# Sequantial_Cell_Switching.net
KiCad netlist of a schematic drawn in Altium Designer
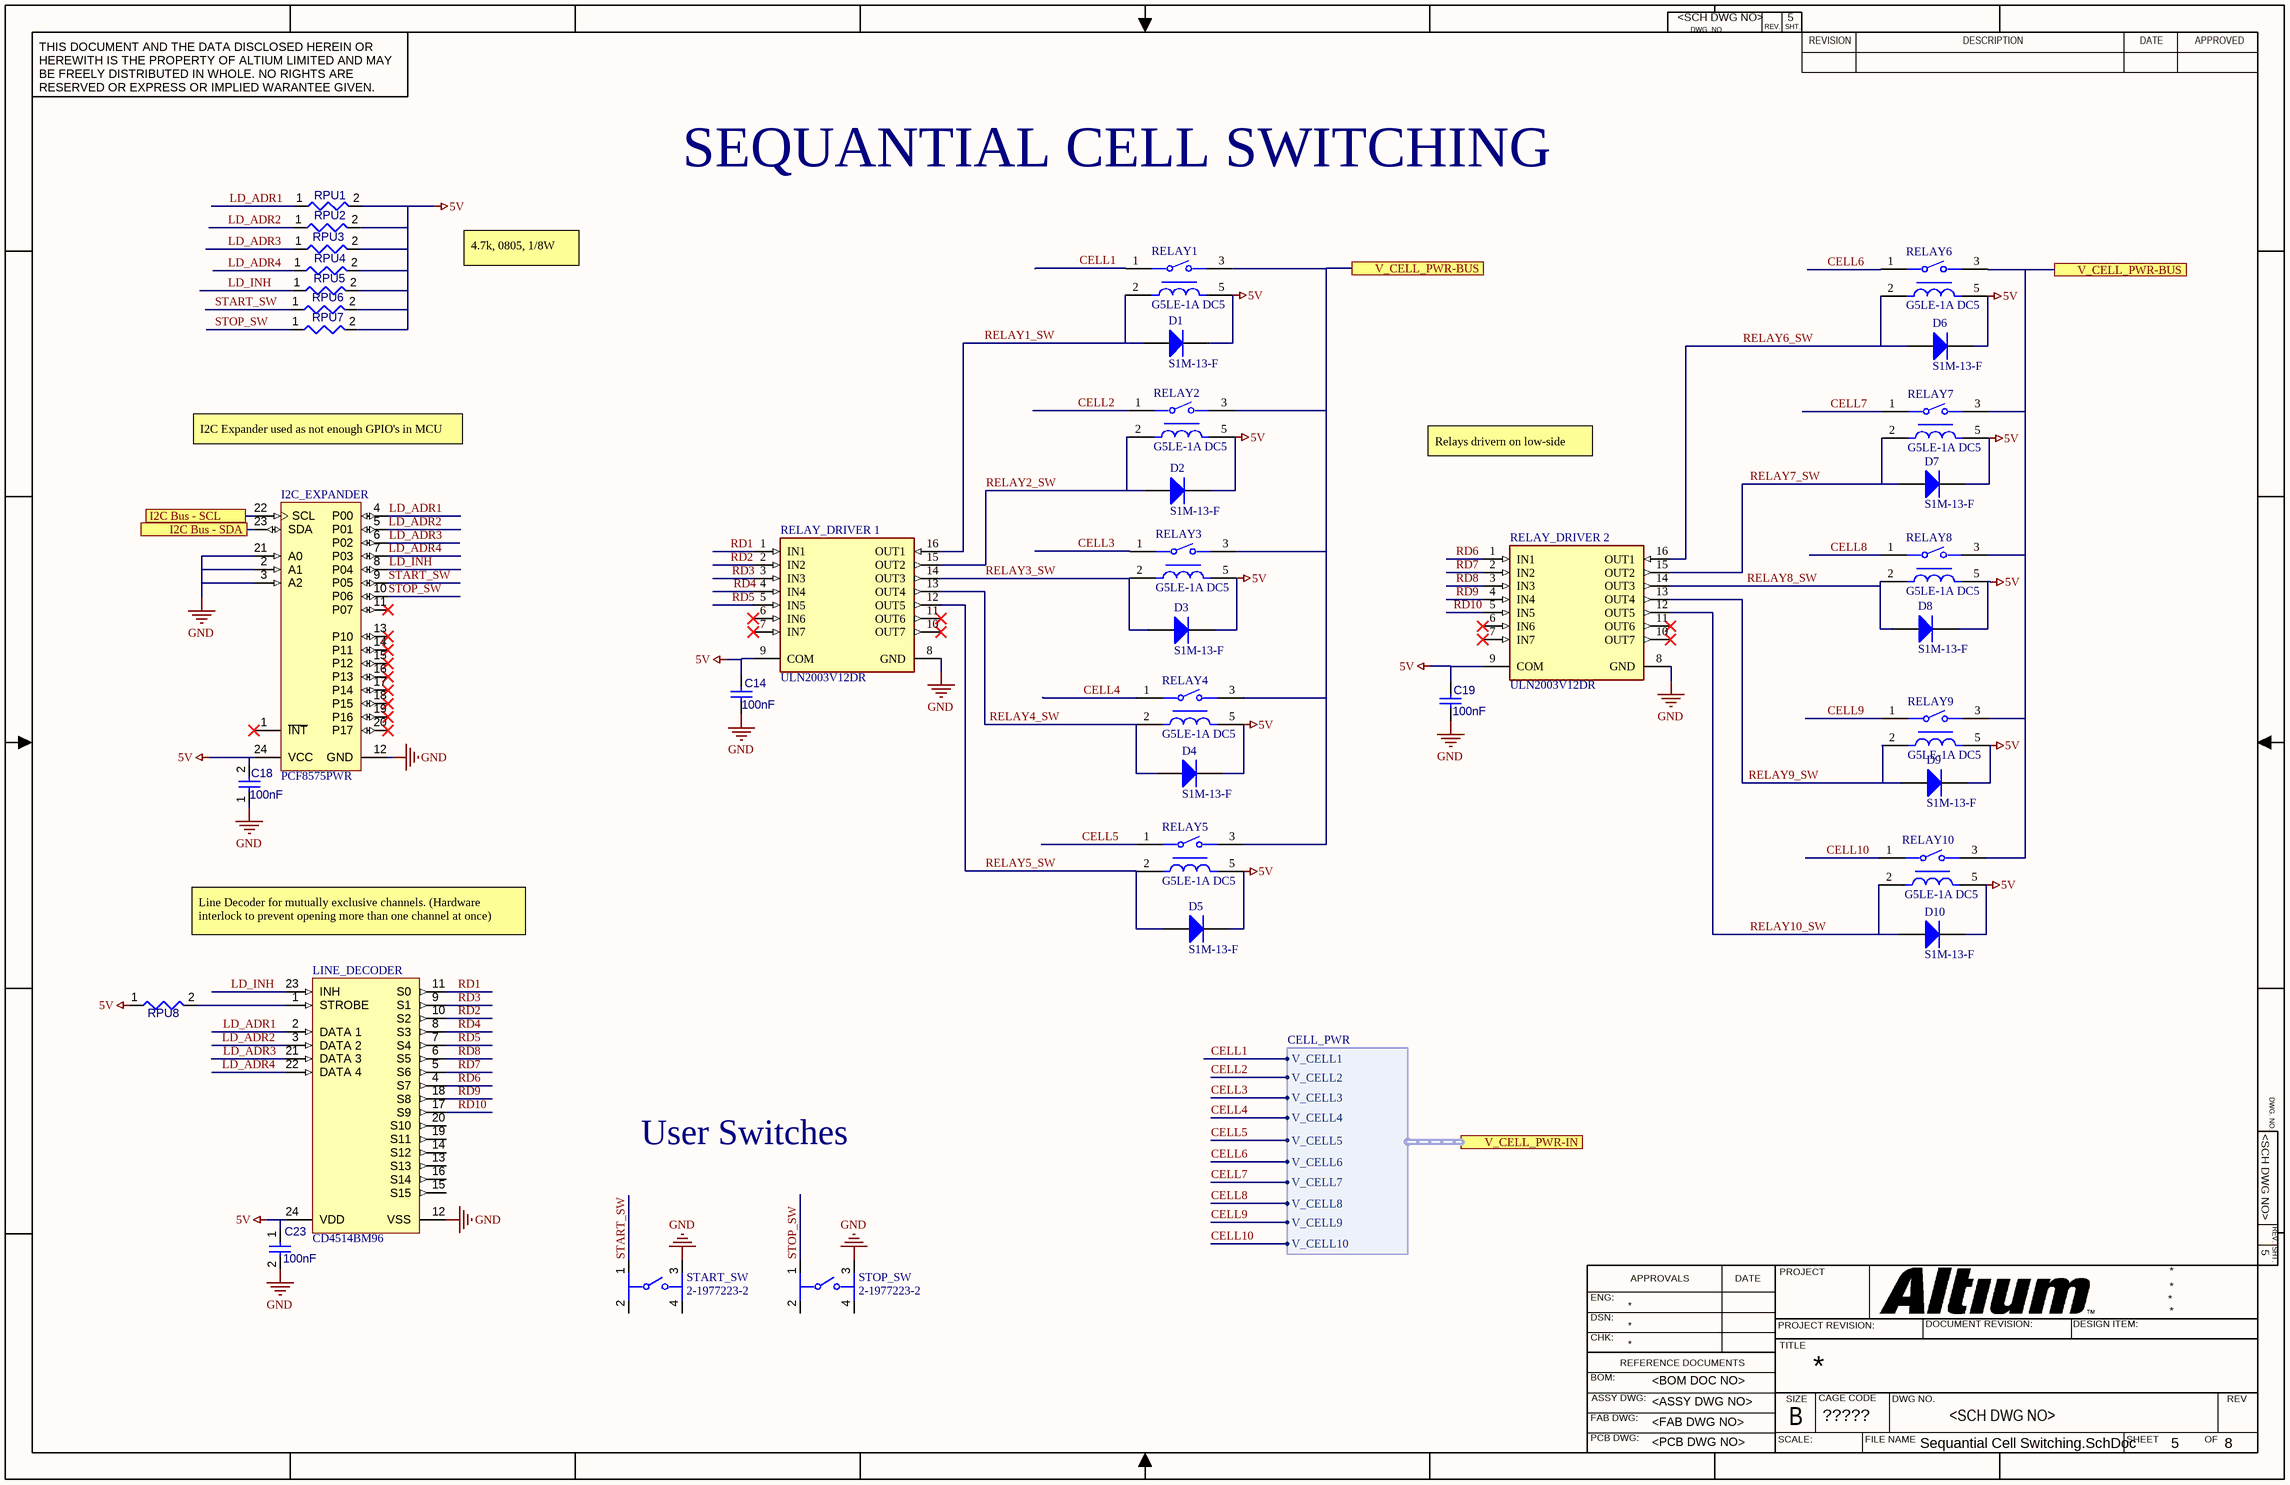
[diagram p0: Sequantial Cell Switching.SchDoc]

(export (version "E")
  (design (tool "Eeschema 10.0.6"))
  (components
    (comp (ref "C14")
      (value "100nF")
      (footprint "CAPC2013X95X50LL10T25")
      (description "Capacitor 100 nF +/-10% 50 V 0805")
      (fields (field (name "TOLERANCE") "10%"))
      (libsource (lib "gugan Sivakumar") (part "CAP-NP-2"))
    )
    (comp (ref "C18")
      (value "100nF")
      (footprint "CAPC2013X95X50LL10T25")
      (description "Capacitor 100 nF +/-10% 50 V 0805")
      (fields (field (name "TOLERANCE") "10%"))
      (libsource (lib "") (part "CAP-NP-2_1"))
    )
    (comp (ref "C19")
      (value "100nF")
      (footprint "CAPC2013X95X50LL10T25")
      (description "Capacitor 100 nF +/-10% 50 V 0805")
      (fields (field (name "TOLERANCE") "10%"))
      (libsource (lib "gugan Sivakumar") (part "CAP-NP-2"))
    )
    (comp (ref "C23")
      (value "100nF")
      (footprint "CAPC2013X95X50LL10T25")
      (description "Capacitor 100 nF +/-10% 50 V 0805")
      (fields (field (name "TOLERANCE") "10%"))
      (libsource (lib "") (part "CAP-NP-2_1"))
    )
    (comp (ref "D1")
      (value "S1M-13-F")
      (footprint "DIOD-S1M-13-F-SMA-2_V")
      (fields (field (name "MANUFACTURER") "Diodes Inc"))
      (libsource (lib "Altium Content Vault") (part "DIOD-D-A1K2-2"))
    )
    (comp (ref "D2")
      (value "S1M-13-F")
      (footprint "DIOD-S1M-13-F-SMA-2_V")
      (fields (field (name "MANUFACTURER") "Diodes Inc"))
      (libsource (lib "Altium Content Vault") (part "DIOD-D-A1K2-2"))
    )
    (comp (ref "D3")
      (value "S1M-13-F")
      (footprint "DIOD-S1M-13-F-SMA-2_V")
      (fields (field (name "MANUFACTURER") "Diodes Inc"))
      (libsource (lib "Altium Content Vault") (part "DIOD-D-A1K2-2"))
    )
    (comp (ref "D4")
      (value "S1M-13-F")
      (footprint "DIOD-S1M-13-F-SMA-2_V")
      (fields (field (name "MANUFACTURER") "Diodes Inc"))
      (libsource (lib "Altium Content Vault") (part "DIOD-D-A1K2-2"))
    )
    (comp (ref "D5")
      (value "S1M-13-F")
      (footprint "DIOD-S1M-13-F-SMA-2_V")
      (fields (field (name "MANUFACTURER") "Diodes Inc"))
      (libsource (lib "Altium Content Vault") (part "DIOD-D-A1K2-2"))
    )
    (comp (ref "D6")
      (value "S1M-13-F")
      (footprint "DIOD-S1M-13-F-SMA-2_V")
      (fields (field (name "MANUFACTURER") "Diodes Inc"))
      (libsource (lib "Altium Content Vault") (part "DIOD-D-A1K2-2"))
    )
    (comp (ref "D7")
      (value "S1M-13-F")
      (footprint "DIOD-S1M-13-F-SMA-2_V")
      (fields (field (name "MANUFACTURER") "Diodes Inc"))
      (libsource (lib "Altium Content Vault") (part "DIOD-D-A1K2-2"))
    )
    (comp (ref "D8")
      (value "S1M-13-F")
      (footprint "DIOD-S1M-13-F-SMA-2_V")
      (fields (field (name "MANUFACTURER") "Diodes Inc"))
      (libsource (lib "Altium Content Vault") (part "DIOD-D-A1K2-2"))
    )
    (comp (ref "D9")
      (value "S1M-13-F")
      (footprint "DIOD-S1M-13-F-SMA-2_V")
      (fields (field (name "MANUFACTURER") "Diodes Inc"))
      (libsource (lib "Altium Content Vault") (part "DIOD-D-A1K2-2"))
    )
    (comp (ref "D10")
      (value "S1M-13-F")
      (footprint "DIOD-S1M-13-F-SMA-2_V")
      (fields (field (name "MANUFACTURER") "Diodes Inc"))
      (libsource (lib "Altium Content Vault") (part "DIOD-D-A1K2-2"))
    )
    (comp (ref "I2C_EXPANDER")
      (value "PCF8575PWR")
      (footprint "PW0024A_L")
      (fields (field (name "MANUFACTURER") "Texas Instruments"))
      (libsource (lib "Altium Content Vault") (part "TI-PCF8575-TSSOP_PW-24"))
    )
    (comp (ref "LINE_DECODER")
      (value "CD4514BM96")
      (footprint "DW0024A_N")
      (description "CMOS 4-Bit Latch/4-to-16 Line Decoder with Output 'High' on Select, DW0024A, LARGE T&R")
      (fields
        (field (name "GENERIC PART NUMBER") "CD4514B")
        (field (name "MANUFACTURER") "Texas Instruments")
      )
      (libsource (lib "Altium Content Vault") (part "TI-CD451XB-24"))
    )
    (comp (ref "RELAY1")
      (value "G5LE-1A DC5")
      (footprint "FP-G5LE-1A_DC5-MFG")
      (description "RELAY GEN PURPOSE SPST 10A 5V")
      (libsource (lib "Altium Content Vault") (part "6e495d724dc645a58f977e2129b87ff"))
    )
    (comp (ref "RELAY2")
      (value "G5LE-1A DC5")
      (footprint "FP-G5LE-1A_DC5-MFG")
      (description "RELAY GEN PURPOSE SPST 10A 5V")
      (libsource (lib "Altium Content Vault") (part "6e495d724dc645a58f977e2129b87ff"))
    )
    (comp (ref "RELAY3")
      (value "G5LE-1A DC5")
      (footprint "FP-G5LE-1A_DC5-MFG")
      (description "RELAY GEN PURPOSE SPST 10A 5V")
      (libsource (lib "Altium Content Vault") (part "6e495d724dc645a58f977e2129b87ff"))
    )
    (comp (ref "RELAY4")
      (value "G5LE-1A DC5")
      (footprint "FP-G5LE-1A_DC5-MFG")
      (description "RELAY GEN PURPOSE SPST 10A 5V")
      (libsource (lib "Altium Content Vault") (part "6e495d724dc645a58f977e2129b87ff"))
    )
    (comp (ref "RELAY5")
      (value "G5LE-1A DC5")
      (footprint "FP-G5LE-1A_DC5-MFG")
      (description "RELAY GEN PURPOSE SPST 10A 5V")
      (libsource (lib "Altium Content Vault") (part "6e495d724dc645a58f977e2129b87ff"))
    )
    (comp (ref "RELAY6")
      (value "G5LE-1A DC5")
      (footprint "FP-G5LE-1A_DC5-MFG")
      (description "RELAY GEN PURPOSE SPST 10A 5V")
      (libsource (lib "Altium Content Vault") (part "6e495d724dc645a58f977e2129b87ff"))
    )
    (comp (ref "RELAY7")
      (value "G5LE-1A DC5")
      (footprint "FP-G5LE-1A_DC5-MFG")
      (description "RELAY GEN PURPOSE SPST 10A 5V")
      (libsource (lib "Altium Content Vault") (part "6e495d724dc645a58f977e2129b87ff"))
    )
    (comp (ref "RELAY8")
      (value "G5LE-1A DC5")
      (footprint "FP-G5LE-1A_DC5-MFG")
      (description "RELAY GEN PURPOSE SPST 10A 5V")
      (libsource (lib "Altium Content Vault") (part "6e495d724dc645a58f977e2129b87ff"))
    )
    (comp (ref "RELAY9")
      (value "G5LE-1A DC5")
      (footprint "FP-G5LE-1A_DC5-MFG")
      (description "RELAY GEN PURPOSE SPST 10A 5V")
      (libsource (lib "Altium Content Vault") (part "6e495d724dc645a58f977e2129b87ff"))
    )
    (comp (ref "RELAY10")
      (value "G5LE-1A DC5")
      (footprint "FP-G5LE-1A_DC5-MFG")
      (description "RELAY GEN PURPOSE SPST 10A 5V")
      (libsource (lib "Altium Content Vault") (part "6e495d724dc645a58f977e2129b87ff"))
    )
    (comp (ref "RELAY_DRIVER 1")
      (value "ULN2003V12DR")
      (footprint "FP-D0016A-MFG")
      (description "MOSFET 7CH 16SOIC")
      (libsource (lib "Altium Content Vault") (part "1bf5c18f3aeaca83cb90dec63c1b343"))
    )
    (comp (ref "RELAY_DRIVER 2")
      (value "ULN2003V12DR")
      (footprint "FP-D0016A-MFG")
      (description "MOSFET 7CH 16SOIC")
      (libsource (lib "Altium Content Vault") (part "1bf5c18f3aeaca83cb90dec63c1b343"))
    )
    (comp (ref "RPU1")
      (value "Resistor 4k7 +/-1% 0805 125 mW")
      (footprint "RESC2013X70X40ML20T20")
      (description "Chip Resistor, 4.7 KOhm, +/- 1%, 0.125 W, -55 to 155 degC, 0805 (2012 Metric)")
      (fields (field (name "TOLERANCE") "1%") (field (name "POWER") "125mW"))
      (libsource (lib "gugan Sivakumar") (part "RES-2"))
    )
    (comp (ref "RPU2")
      (value "Resistor 4k7 +/-1% 0805 125 mW")
      (footprint "RESC2013X70X40ML20T20")
      (description "Chip Resistor, 4.7 KOhm, +/- 1%, 0.125 W, -55 to 155 degC, 0805 (2012 Metric)")
      (fields (field (name "TOLERANCE") "1%") (field (name "POWER") "125mW"))
      (libsource (lib "gugan Sivakumar") (part "RES-2"))
    )
    (comp (ref "RPU3")
      (value "Resistor 4k7 +/-1% 0805 125 mW")
      (footprint "RESC2013X70X40ML20T20")
      (description "Chip Resistor, 4.7 KOhm, +/- 1%, 0.125 W, -55 to 155 degC, 0805 (2012 Metric)")
      (fields (field (name "TOLERANCE") "1%") (field (name "POWER") "125mW"))
      (libsource (lib "gugan Sivakumar") (part "RES-2"))
    )
    (comp (ref "RPU4")
      (value "Resistor 4k7 +/-1% 0805 125 mW")
      (footprint "RESC2013X70X40ML20T20")
      (description "Chip Resistor, 4.7 KOhm, +/- 1%, 0.125 W, -55 to 155 degC, 0805 (2012 Metric)")
      (fields (field (name "TOLERANCE") "1%") (field (name "POWER") "125mW"))
      (libsource (lib "gugan Sivakumar") (part "RES-2"))
    )
    (comp (ref "RPU5")
      (value "Resistor 4k7 +/-1% 0805 125 mW")
      (footprint "RESC2013X70X40ML20T20")
      (description "Chip Resistor, 4.7 KOhm, +/- 1%, 0.125 W, -55 to 155 degC, 0805 (2012 Metric)")
      (fields (field (name "TOLERANCE") "1%") (field (name "POWER") "125mW"))
      (libsource (lib "gugan Sivakumar") (part "RES-2"))
    )
    (comp (ref "RPU6")
      (value "Resistor 4k7 +/-1% 0805 125 mW")
      (footprint "RESC2013X70X40ML20T20")
      (description "Chip Resistor, 4.7 KOhm, +/- 1%, 0.125 W, -55 to 155 degC, 0805 (2012 Metric)")
      (fields (field (name "TOLERANCE") "1%") (field (name "POWER") "125mW"))
      (libsource (lib "gugan Sivakumar") (part "RES-2"))
    )
    (comp (ref "RPU7")
      (value "Resistor 4k7 +/-1% 0805 125 mW")
      (footprint "RESC2013X70X40ML20T20")
      (description "Chip Resistor, 4.7 KOhm, +/- 1%, 0.125 W, -55 to 155 degC, 0805 (2012 Metric)")
      (fields (field (name "TOLERANCE") "1%") (field (name "POWER") "125mW"))
      (libsource (lib "gugan Sivakumar") (part "RES-2"))
    )
    (comp (ref "RPU8")
      (value "Resistor 4k7 +/-1% 0805 125 mW")
      (footprint "RESC2013X70X40ML20T20")
      (description "Chip Resistor, 4.7 KOhm, +/- 1%, 0.125 W, -55 to 155 degC, 0805 (2012 Metric)")
      (fields (field (name "TOLERANCE") "1%") (field (name "POWER") "125mW"))
      (libsource (lib "gugan Sivakumar") (part "RES-2"))
    )
    (comp (ref "START_SW")
      (value "2-1977223-2")
      (footprint "FP-2-1977223-2-MFG")
      (description "SWITCH TACTILE SPST-NO 0.05A 24V")
      (libsource (lib "Altium Content Vault") (part "b8895f3f4cefb76e1819d2863dba89b"))
    )
    (comp (ref "STOP_SW")
      (value "2-1977223-2")
      (footprint "FP-2-1977223-2-MFG")
      (description "SWITCH TACTILE SPST-NO 0.05A 24V")
      (libsource (lib "Altium Content Vault") (part "b8895f3f4cefb76e1819d2863dba89b"))
    )
  )
  (nets
    (net (code "2") (name "/CELL1") (class "Default")
      (node (ref "RELAY1") (pin "1") (pinfunction "1_1") (pintype "passive"))
    )
    (net (code "3") (name "/CELL2") (class "Default")
      (node (ref "RELAY2") (pin "1") (pinfunction "1_1") (pintype "passive"))
    )
    (net (code "4") (name "/CELL3") (class "Default")
      (node (ref "RELAY3") (pin "1") (pinfunction "1_1") (pintype "passive"))
    )
    (net (code "5") (name "/CELL4") (class "Default")
      (node (ref "RELAY4") (pin "1") (pinfunction "1_1") (pintype "passive"))
    )
    (net (code "6") (name "/CELL5") (class "Default")
      (node (ref "RELAY5") (pin "1") (pinfunction "1_1") (pintype "passive"))
    )
    (net (code "7") (name "/CELL6") (class "Default")
      (node (ref "RELAY6") (pin "1") (pinfunction "1_1") (pintype "passive"))
    )
    (net (code "8") (name "/CELL7") (class "Default")
      (node (ref "RELAY7") (pin "1") (pinfunction "1_1") (pintype "passive"))
    )
    (net (code "9") (name "/CELL8") (class "Default")
      (node (ref "RELAY8") (pin "1") (pinfunction "1_1") (pintype "passive"))
    )
    (net (code "10") (name "/CELL9") (class "Default")
      (node (ref "RELAY9") (pin "1") (pinfunction "1_1") (pintype "passive"))
    )
    (net (code "11") (name "/CELL10") (class "Default")
      (node (ref "RELAY10") (pin "1") (pinfunction "1_1") (pintype "passive"))
    )
    (net (code "12") (name "/I2C Bus - SCL") (class "Default")
      (node (ref "I2C_EXPANDER") (pin "22") (pinfunction "SCL_22") (pintype "input"))
    )
    (net (code "13") (name "/I2C Bus - SDA") (class "Default")
      (node (ref "I2C_EXPANDER") (pin "23") (pinfunction "SDA_23") (pintype "bidirectional"))
    )
    (net (code "14") (name "/LD_ADR1") (class "Default")
      (node (ref "I2C_EXPANDER") (pin "4") (pinfunction "P00_4") (pintype "bidirectional"))
      (node (ref "LINE_DECODER") (pin "2") (pinfunction "DATA_1_2") (pintype "input"))
      (node (ref "RPU1") (pin "1") (pinfunction "1_1") (pintype "passive"))
    )
    (net (code "15") (name "/LD_ADR2") (class "Default")
      (node (ref "I2C_EXPANDER") (pin "5") (pinfunction "P01_5") (pintype "bidirectional"))
      (node (ref "LINE_DECODER") (pin "3") (pinfunction "DATA_2_3") (pintype "input"))
      (node (ref "RPU2") (pin "1") (pinfunction "1_1") (pintype "passive"))
    )
    (net (code "16") (name "/LD_ADR3") (class "Default")
      (node (ref "I2C_EXPANDER") (pin "6") (pinfunction "P02_6") (pintype "bidirectional"))
      (node (ref "LINE_DECODER") (pin "21") (pinfunction "DATA_3_21") (pintype "input"))
      (node (ref "RPU3") (pin "1") (pinfunction "1_1") (pintype "passive"))
    )
    (net (code "17") (name "/LD_ADR4") (class "Default")
      (node (ref "I2C_EXPANDER") (pin "7") (pinfunction "P03_7") (pintype "bidirectional"))
      (node (ref "LINE_DECODER") (pin "22") (pinfunction "DATA_4_22") (pintype "input"))
      (node (ref "RPU4") (pin "1") (pinfunction "1_1") (pintype "passive"))
    )
    (net (code "18") (name "/LD_INH") (class "Default")
      (node (ref "I2C_EXPANDER") (pin "8") (pinfunction "P04_8") (pintype "bidirectional"))
      (node (ref "LINE_DECODER") (pin "23") (pinfunction "INH_23") (pintype "input"))
      (node (ref "RPU5") (pin "1") (pinfunction "1_1") (pintype "passive"))
    )
    (net (code "19") (name "/RD1") (class "Default")
      (node (ref "LINE_DECODER") (pin "11") (pinfunction "S0_11") (pintype "output"))
      (node (ref "RELAY_DRIVER 1") (pin "1") (pinfunction "IN1_1") (pintype "input"))
    )
    (net (code "20") (name "/RD2") (class "Default")
      (node (ref "LINE_DECODER") (pin "10") (pinfunction "S2_10") (pintype "output"))
      (node (ref "RELAY_DRIVER 1") (pin "2") (pinfunction "IN2_2") (pintype "input"))
    )
    (net (code "21") (name "/RD3") (class "Default")
      (node (ref "LINE_DECODER") (pin "9") (pinfunction "S1_9") (pintype "output"))
      (node (ref "RELAY_DRIVER 1") (pin "3") (pinfunction "IN3_3") (pintype "input"))
    )
    (net (code "22") (name "/RD4") (class "Default")
      (node (ref "LINE_DECODER") (pin "8") (pinfunction "S3_8") (pintype "output"))
      (node (ref "RELAY_DRIVER 1") (pin "4") (pinfunction "IN4_4") (pintype "input"))
    )
    (net (code "23") (name "/RD5") (class "Default")
      (node (ref "LINE_DECODER") (pin "7") (pinfunction "S4_7") (pintype "output"))
      (node (ref "RELAY_DRIVER 1") (pin "5") (pinfunction "IN5_5") (pintype "input"))
    )
    (net (code "24") (name "/RD6") (class "Default")
      (node (ref "LINE_DECODER") (pin "4") (pinfunction "S7_4") (pintype "output"))
      (node (ref "RELAY_DRIVER 2") (pin "1") (pinfunction "IN1_1") (pintype "input"))
    )
    (net (code "25") (name "/RD7") (class "Default")
      (node (ref "LINE_DECODER") (pin "5") (pinfunction "S6_5") (pintype "output"))
      (node (ref "RELAY_DRIVER 2") (pin "2") (pinfunction "IN2_2") (pintype "input"))
    )
    (net (code "26") (name "/RD8") (class "Default")
      (node (ref "LINE_DECODER") (pin "6") (pinfunction "S5_6") (pintype "output"))
      (node (ref "RELAY_DRIVER 2") (pin "3") (pinfunction "IN3_3") (pintype "input"))
    )
    (net (code "27") (name "/RD9") (class "Default")
      (node (ref "LINE_DECODER") (pin "18") (pinfunction "S8_18") (pintype "output"))
      (node (ref "RELAY_DRIVER 2") (pin "4") (pinfunction "IN4_4") (pintype "input"))
    )
    (net (code "28") (name "/RD10") (class "Default")
      (node (ref "LINE_DECODER") (pin "17") (pinfunction "S9_17") (pintype "output"))
      (node (ref "RELAY_DRIVER 2") (pin "5") (pinfunction "IN5_5") (pintype "input"))
    )
    (net (code "29") (name "/RELAY1_SW") (class "Default")
      (node (ref "D1") (pin "1") (pinfunction "A_1") (pintype "passive"))
      (node (ref "RELAY1") (pin "2") (pinfunction "2_2") (pintype "passive"))
      (node (ref "RELAY_DRIVER 1") (pin "16") (pinfunction "OUT1_16") (pintype "input"))
    )
    (net (code "30") (name "/RELAY2_SW") (class "Default")
      (node (ref "D2") (pin "1") (pinfunction "A_1") (pintype "passive"))
      (node (ref "RELAY2") (pin "2") (pinfunction "2_2") (pintype "passive"))
      (node (ref "RELAY_DRIVER 1") (pin "15") (pinfunction "OUT2_15") (pintype "output"))
    )
    (net (code "31") (name "/RELAY3_SW") (class "Default")
      (node (ref "D3") (pin "1") (pinfunction "A_1") (pintype "passive"))
      (node (ref "RELAY3") (pin "2") (pinfunction "2_2") (pintype "passive"))
      (node (ref "RELAY_DRIVER 1") (pin "14") (pinfunction "OUT3_14") (pintype "output"))
    )
    (net (code "32") (name "/RELAY4_SW") (class "Default")
      (node (ref "D4") (pin "1") (pinfunction "A_1") (pintype "passive"))
      (node (ref "RELAY4") (pin "2") (pinfunction "2_2") (pintype "passive"))
      (node (ref "RELAY_DRIVER 1") (pin "13") (pinfunction "OUT4_13") (pintype "output"))
    )
    (net (code "33") (name "/RELAY5_SW") (class "Default")
      (node (ref "D5") (pin "1") (pinfunction "A_1") (pintype "passive"))
      (node (ref "RELAY5") (pin "2") (pinfunction "2_2") (pintype "passive"))
      (node (ref "RELAY_DRIVER 1") (pin "12") (pinfunction "OUT5_12") (pintype "output"))
    )
    (net (code "34") (name "/RELAY6_SW") (class "Default")
      (node (ref "D6") (pin "1") (pinfunction "A_1") (pintype "passive"))
      (node (ref "RELAY6") (pin "2") (pinfunction "2_2") (pintype "passive"))
      (node (ref "RELAY_DRIVER 2") (pin "16") (pinfunction "OUT1_16") (pintype "input"))
    )
    (net (code "35") (name "/RELAY7_SW") (class "Default")
      (node (ref "D7") (pin "1") (pinfunction "A_1") (pintype "passive"))
      (node (ref "RELAY7") (pin "2") (pinfunction "2_2") (pintype "passive"))
      (node (ref "RELAY_DRIVER 2") (pin "15") (pinfunction "OUT2_15") (pintype "output"))
    )
    (net (code "36") (name "/RELAY8_SW") (class "Default")
      (node (ref "D8") (pin "1") (pinfunction "A_1") (pintype "passive"))
      (node (ref "RELAY8") (pin "2") (pinfunction "2_2") (pintype "passive"))
      (node (ref "RELAY_DRIVER 2") (pin "14") (pinfunction "OUT3_14") (pintype "output"))
    )
    (net (code "37") (name "/RELAY9_SW") (class "Default")
      (node (ref "D9") (pin "1") (pinfunction "A_1") (pintype "passive"))
      (node (ref "RELAY9") (pin "2") (pinfunction "2_2") (pintype "passive"))
      (node (ref "RELAY_DRIVER 2") (pin "13") (pinfunction "OUT4_13") (pintype "output"))
    )
    (net (code "38") (name "/RELAY10_SW") (class "Default")
      (node (ref "D10") (pin "1") (pinfunction "A_1") (pintype "passive"))
      (node (ref "RELAY10") (pin "2") (pinfunction "2_2") (pintype "passive"))
      (node (ref "RELAY_DRIVER 2") (pin "12") (pinfunction "OUT5_12") (pintype "output"))
    )
    (net (code "39") (name "/START_SW") (class "Default")
      (node (ref "I2C_EXPANDER") (pin "9") (pinfunction "P05_9") (pintype "bidirectional"))
      (node (ref "RPU6") (pin "1") (pinfunction "1_1") (pintype "passive"))
      (node (ref "START_SW") (pin "1") (pinfunction "1_1") (pintype "passive"))
    )
    (net (code "40") (name "/STOP_SW") (class "Default")
      (node (ref "I2C_EXPANDER") (pin "10") (pinfunction "P06_10") (pintype "bidirectional"))
      (node (ref "RPU7") (pin "1") (pinfunction "1_1") (pintype "passive"))
      (node (ref "STOP_SW") (pin "1") (pinfunction "1_1") (pintype "passive"))
    )
    (net (code "41") (name "/V_CELL_PWR-BUS") (class "Default")
      (node (ref "RELAY1") (pin "3") (pinfunction "3_3") (pintype "passive"))
      (node (ref "RELAY10") (pin "3") (pinfunction "3_3") (pintype "passive"))
      (node (ref "RELAY2") (pin "3") (pinfunction "3_3") (pintype "passive"))
      (node (ref "RELAY3") (pin "3") (pinfunction "3_3") (pintype "passive"))
      (node (ref "RELAY4") (pin "3") (pinfunction "3_3") (pintype "passive"))
      (node (ref "RELAY5") (pin "3") (pinfunction "3_3") (pintype "passive"))
      (node (ref "RELAY6") (pin "3") (pinfunction "3_3") (pintype "passive"))
      (node (ref "RELAY7") (pin "3") (pinfunction "3_3") (pintype "passive"))
      (node (ref "RELAY8") (pin "3") (pinfunction "3_3") (pintype "passive"))
      (node (ref "RELAY9") (pin "3") (pinfunction "3_3") (pintype "passive"))
    )
    (net (code "43") (name "5V") (class "Default")
      (node (ref "C14") (pin "2") (pinfunction "2_2") (pintype "passive"))
      (node (ref "C18") (pin "2") (pinfunction "2_2") (pintype "passive"))
      (node (ref "C19") (pin "2") (pinfunction "2_2") (pintype "passive"))
      (node (ref "C23") (pin "1") (pinfunction "1_1") (pintype "passive"))
      (node (ref "D1") (pin "2") (pinfunction "K_2") (pintype "passive"))
      (node (ref "D10") (pin "2") (pinfunction "K_2") (pintype "passive"))
      (node (ref "D2") (pin "2") (pinfunction "K_2") (pintype "passive"))
      (node (ref "D3") (pin "2") (pinfunction "K_2") (pintype "passive"))
      (node (ref "D4") (pin "2") (pinfunction "K_2") (pintype "passive"))
      (node (ref "D5") (pin "2") (pinfunction "K_2") (pintype "passive"))
      (node (ref "D6") (pin "2") (pinfunction "K_2") (pintype "passive"))
      (node (ref "D7") (pin "2") (pinfunction "K_2") (pintype "passive"))
      (node (ref "D8") (pin "2") (pinfunction "K_2") (pintype "passive"))
      (node (ref "D9") (pin "2") (pinfunction "K_2") (pintype "passive"))
      (node (ref "I2C_EXPANDER") (pin "24") (pinfunction "VCC_24") (pintype "power_in"))
      (node (ref "LINE_DECODER") (pin "24") (pinfunction "VDD_24") (pintype "power_in"))
      (node (ref "RELAY1") (pin "5") (pinfunction "5_5") (pintype "passive"))
      (node (ref "RELAY10") (pin "5") (pinfunction "5_5") (pintype "passive"))
      (node (ref "RELAY2") (pin "5") (pinfunction "5_5") (pintype "passive"))
      (node (ref "RELAY3") (pin "5") (pinfunction "5_5") (pintype "passive"))
      (node (ref "RELAY4") (pin "5") (pinfunction "5_5") (pintype "passive"))
      (node (ref "RELAY5") (pin "5") (pinfunction "5_5") (pintype "passive"))
      (node (ref "RELAY6") (pin "5") (pinfunction "5_5") (pintype "passive"))
      (node (ref "RELAY7") (pin "5") (pinfunction "5_5") (pintype "passive"))
      (node (ref "RELAY8") (pin "5") (pinfunction "5_5") (pintype "passive"))
      (node (ref "RELAY9") (pin "5") (pinfunction "5_5") (pintype "passive"))
      (node (ref "RELAY_DRIVER 1") (pin "9") (pinfunction "COM_9") (pintype "passive"))
      (node (ref "RELAY_DRIVER 2") (pin "9") (pinfunction "COM_9") (pintype "passive"))
      (node (ref "RPU1") (pin "2") (pinfunction "2_2") (pintype "passive"))
      (node (ref "RPU2") (pin "2") (pinfunction "2_2") (pintype "passive"))
      (node (ref "RPU3") (pin "2") (pinfunction "2_2") (pintype "passive"))
      (node (ref "RPU4") (pin "2") (pinfunction "2_2") (pintype "passive"))
      (node (ref "RPU5") (pin "2") (pinfunction "2_2") (pintype "passive"))
      (node (ref "RPU6") (pin "2") (pinfunction "2_2") (pintype "passive"))
      (node (ref "RPU7") (pin "2") (pinfunction "2_2") (pintype "passive"))
      (node (ref "RPU8") (pin "1") (pinfunction "1_1") (pintype "passive"))
    )
    (net (code "44") (name "GND") (class "Default")
      (node (ref "C14") (pin "1") (pinfunction "1_1") (pintype "passive"))
      (node (ref "C18") (pin "1") (pinfunction "1_1") (pintype "passive"))
      (node (ref "C19") (pin "1") (pinfunction "1_1") (pintype "passive"))
      (node (ref "C23") (pin "2") (pinfunction "2_2") (pintype "passive"))
      (node (ref "I2C_EXPANDER") (pin "12") (pinfunction "GND_12") (pintype "power_in"))
      (node (ref "I2C_EXPANDER") (pin "2") (pinfunction "A1_2") (pintype "input"))
      (node (ref "I2C_EXPANDER") (pin "21") (pinfunction "A0_21") (pintype "input"))
      (node (ref "I2C_EXPANDER") (pin "3") (pinfunction "A2_3") (pintype "input"))
      (node (ref "LINE_DECODER") (pin "12") (pinfunction "VSS_12") (pintype "power_in"))
      (node (ref "RELAY_DRIVER 1") (pin "8") (pinfunction "GND_8") (pintype "power_in"))
      (node (ref "RELAY_DRIVER 2") (pin "8") (pinfunction "GND_8") (pintype "power_in"))
      (node (ref "START_SW") (pin "3") (pinfunction "3_3") (pintype "passive"))
      (node (ref "STOP_SW") (pin "3") (pinfunction "3_3") (pintype "passive"))
    )
    (net (code "45") (name "Net-(LINE_DECODER-STROBE)") (class "Default")
      (node (ref "LINE_DECODER") (pin "1") (pinfunction "STROBE_1") (pintype "input"))
      (node (ref "RPU8") (pin "2") (pinfunction "2_2") (pintype "passive"))
    )
    (net (code "46") (name "unconnected-(I2C_EXPANDER-P07-Pad11)") (class "Default")
      (node (ref "I2C_EXPANDER") (pin "11") (pinfunction "P07_11") (pintype "bidirectional+no_connect"))
    )
    (net (code "47") (name "unconnected-(I2C_EXPANDER-P10-Pad13)") (class "Default")
      (node (ref "I2C_EXPANDER") (pin "13") (pinfunction "P10_13") (pintype "bidirectional+no_connect"))
    )
    (net (code "48") (name "unconnected-(I2C_EXPANDER-P11-Pad14)") (class "Default")
      (node (ref "I2C_EXPANDER") (pin "14") (pinfunction "P11_14") (pintype "bidirectional+no_connect"))
    )
    (net (code "49") (name "unconnected-(I2C_EXPANDER-P12-Pad15)") (class "Default")
      (node (ref "I2C_EXPANDER") (pin "15") (pinfunction "P12_15") (pintype "bidirectional+no_connect"))
    )
    (net (code "50") (name "unconnected-(I2C_EXPANDER-P13-Pad16)") (class "Default")
      (node (ref "I2C_EXPANDER") (pin "16") (pinfunction "P13_16") (pintype "bidirectional+no_connect"))
    )
    (net (code "51") (name "unconnected-(I2C_EXPANDER-P14-Pad17)") (class "Default")
      (node (ref "I2C_EXPANDER") (pin "17") (pinfunction "P14_17") (pintype "bidirectional+no_connect"))
    )
    (net (code "52") (name "unconnected-(I2C_EXPANDER-P15-Pad18)") (class "Default")
      (node (ref "I2C_EXPANDER") (pin "18") (pinfunction "P15_18") (pintype "bidirectional+no_connect"))
    )
    (net (code "53") (name "unconnected-(I2C_EXPANDER-P16-Pad19)") (class "Default")
      (node (ref "I2C_EXPANDER") (pin "19") (pinfunction "P16_19") (pintype "bidirectional+no_connect"))
    )
    (net (code "54") (name "unconnected-(I2C_EXPANDER-P17-Pad20)") (class "Default")
      (node (ref "I2C_EXPANDER") (pin "20") (pinfunction "P17_20") (pintype "bidirectional+no_connect"))
    )
    (net (code "55") (name "unconnected-(I2C_EXPANDER-~{INT}-Pad1)") (class "Default")
      (node (ref "I2C_EXPANDER") (pin "1") (pinfunction "~{INT}_1") (pintype "open_collector+no_connect"))
    )
    (net (code "56") (name "unconnected-(LINE_DECODER-S10-Pad20)") (class "Default")
      (node (ref "LINE_DECODER") (pin "20") (pinfunction "S10_20") (pintype "output"))
    )
    (net (code "57") (name "unconnected-(LINE_DECODER-S11-Pad19)") (class "Default")
      (node (ref "LINE_DECODER") (pin "19") (pinfunction "S11_19") (pintype "output"))
    )
    (net (code "58") (name "unconnected-(LINE_DECODER-S12-Pad14)") (class "Default")
      (node (ref "LINE_DECODER") (pin "14") (pinfunction "S12_14") (pintype "output"))
    )
    (net (code "59") (name "unconnected-(LINE_DECODER-S13-Pad13)") (class "Default")
      (node (ref "LINE_DECODER") (pin "13") (pinfunction "S13_13") (pintype "output"))
    )
    (net (code "60") (name "unconnected-(LINE_DECODER-S14-Pad16)") (class "Default")
      (node (ref "LINE_DECODER") (pin "16") (pinfunction "S14_16") (pintype "output"))
    )
    (net (code "61") (name "unconnected-(LINE_DECODER-S15-Pad15)") (class "Default")
      (node (ref "LINE_DECODER") (pin "15") (pinfunction "S15_15") (pintype "output"))
    )
    (net (code "62") (name "unconnected-(RELAY_DRIVER 1-IN6-Pad6)") (class "Default")
      (node (ref "RELAY_DRIVER 1") (pin "6") (pinfunction "IN6_6") (pintype "input+no_connect"))
    )
    (net (code "63") (name "unconnected-(RELAY_DRIVER 1-IN7-Pad7)") (class "Default")
      (node (ref "RELAY_DRIVER 1") (pin "7") (pinfunction "IN7_7") (pintype "input+no_connect"))
    )
    (net (code "64") (name "unconnected-(RELAY_DRIVER 1-OUT6-Pad11)") (class "Default")
      (node (ref "RELAY_DRIVER 1") (pin "11") (pinfunction "OUT6_11") (pintype "output+no_connect"))
    )
    (net (code "65") (name "unconnected-(RELAY_DRIVER 1-OUT7-Pad10)") (class "Default")
      (node (ref "RELAY_DRIVER 1") (pin "10") (pinfunction "OUT7_10") (pintype "output+no_connect"))
    )
    (net (code "66") (name "unconnected-(RELAY_DRIVER 2-IN6-Pad6)") (class "Default")
      (node (ref "RELAY_DRIVER 2") (pin "6") (pinfunction "IN6_6") (pintype "input+no_connect"))
    )
    (net (code "67") (name "unconnected-(RELAY_DRIVER 2-IN7-Pad7)") (class "Default")
      (node (ref "RELAY_DRIVER 2") (pin "7") (pinfunction "IN7_7") (pintype "input+no_connect"))
    )
    (net (code "68") (name "unconnected-(RELAY_DRIVER 2-OUT6-Pad11)") (class "Default")
      (node (ref "RELAY_DRIVER 2") (pin "11") (pinfunction "OUT6_11") (pintype "output+no_connect"))
    )
    (net (code "69") (name "unconnected-(RELAY_DRIVER 2-OUT7-Pad10)") (class "Default")
      (node (ref "RELAY_DRIVER 2") (pin "10") (pinfunction "OUT7_10") (pintype "output+no_connect"))
    )
    (net (code "70") (name "unconnected-(START_SW-Pad2)") (class "Default")
      (node (ref "START_SW") (pin "2") (pinfunction "2_2") (pintype "passive"))
    )
    (net (code "71") (name "unconnected-(START_SW-Pad4)") (class "Default")
      (node (ref "START_SW") (pin "4") (pinfunction "4_4") (pintype "passive"))
    )
    (net (code "72") (name "unconnected-(STOP_SW-Pad2)") (class "Default")
      (node (ref "STOP_SW") (pin "2") (pinfunction "2_2") (pintype "passive"))
    )
    (net (code "73") (name "unconnected-(STOP_SW-Pad4)") (class "Default")
      (node (ref "STOP_SW") (pin "4") (pinfunction "4_4") (pintype "passive"))
    )
  )
)
